# CH2-Isolation.net
KiCad netlist of a schematic drawn in Altium Designer
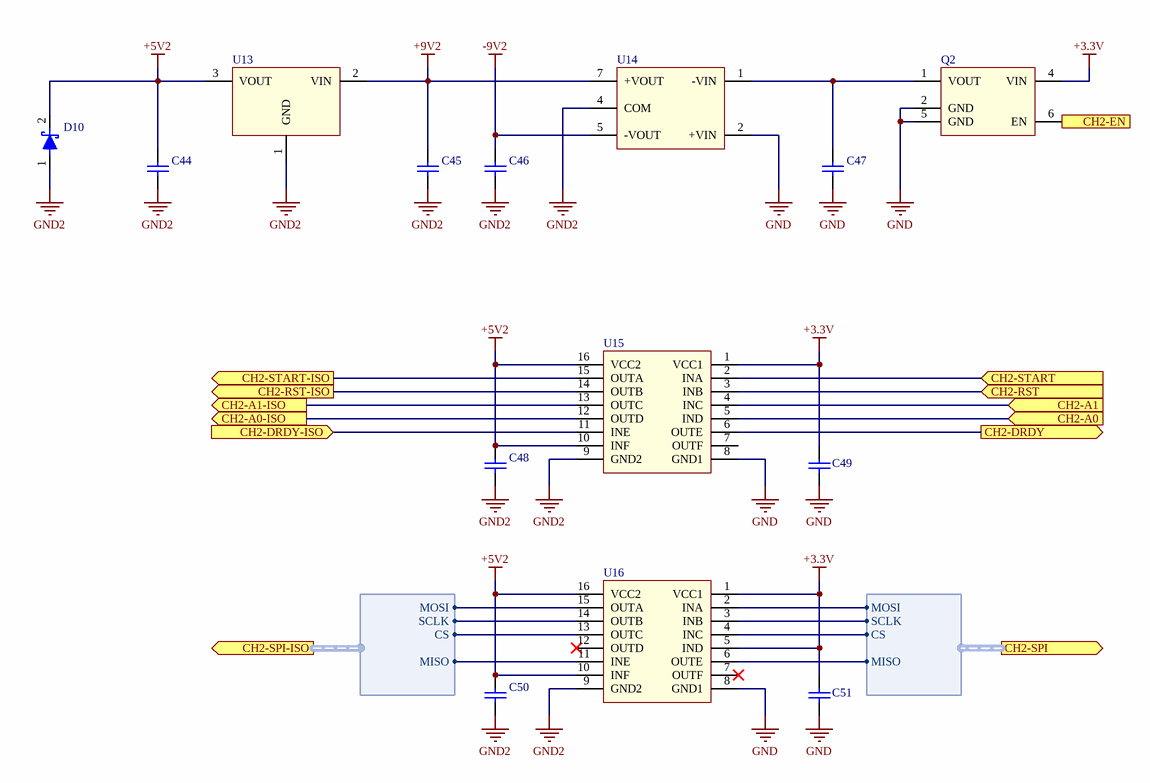
[diagram p0: CH2-Isolation.SchDoc]

(export (version "E")
  (design (tool "Eeschema 10.0.6"))
  (components
    (comp (ref "C44")
      (value "C0603C105M3RAC7867")
      (footprint "CAP-0603")
      (description "CAP CER 1uF 25V X7R 0603")
      (fields (field (name "MANUFACTURER") "Kemet") (field (name "TOLERANCE") "20%"))
      (libsource (lib "Kemet") (part "C0603C105M3RAC7867"))
    )
    (comp (ref "C45")
      (value "C0603C105M3RAC7867")
      (footprint "CAP-0603")
      (description "CAP CER 1uF 25V X7R 0603")
      (fields (field (name "MANUFACTURER") "Kemet") (field (name "TOLERANCE") "20%"))
      (libsource (lib "Kemet") (part "C0603C105M3RAC7867"))
    )
    (comp (ref "C46")
      (value "C0603C105M3RAC7867")
      (footprint "CAP-0603")
      (description "CAP CER 1uF 25V X7R 0603")
      (fields (field (name "MANUFACTURER") "Kemet") (field (name "TOLERANCE") "20%"))
      (libsource (lib "Kemet") (part "C0603C105M3RAC7867"))
    )
    (comp (ref "C47")
      (value "C0603C105M3RAC7867")
      (footprint "CAP-0603")
      (description "CAP CER 1uF 25V X7R 0603")
      (fields (field (name "MANUFACTURER") "Kemet") (field (name "TOLERANCE") "20%"))
      (libsource (lib "Kemet") (part "C0603C105M3RAC7867"))
    )
    (comp (ref "C48")
      (value "C0603C105M3RAC7867")
      (footprint "CAP-0603")
      (description "CAP CER 1uF 25V X7R 0603")
      (fields (field (name "MANUFACTURER") "Kemet") (field (name "TOLERANCE") "20%"))
      (libsource (lib "Kemet") (part "C0603C105M3RAC7867"))
    )
    (comp (ref "C49")
      (value "C0603C105M3RAC7867")
      (footprint "CAP-0603")
      (description "CAP CER 1uF 25V X7R 0603")
      (fields (field (name "MANUFACTURER") "Kemet") (field (name "TOLERANCE") "20%"))
      (libsource (lib "Kemet") (part "C0603C105M3RAC7867"))
    )
    (comp (ref "C50")
      (value "C0603C105M3RAC7867")
      (footprint "CAP-0603")
      (description "CAP CER 1uF 25V X7R 0603")
      (fields (field (name "MANUFACTURER") "Kemet") (field (name "TOLERANCE") "20%"))
      (libsource (lib "Kemet") (part "C0603C105M3RAC7867"))
    )
    (comp (ref "C51")
      (value "C0603C105M3RAC7867")
      (footprint "CAP-0603")
      (description "CAP CER 1uF 25V X7R 0603")
      (fields (field (name "MANUFACTURER") "Kemet") (field (name "TOLERANCE") "20%"))
      (libsource (lib "Kemet") (part "C0603C105M3RAC7867"))
    )
    (comp (ref "D10")
      (value "~")
      (footprint "SOD323 - DIODE UNIDIR")
      (description "Schottky Diode 30V 200mA SOT323")
      (fields (field (name "MANUFACTURER") "OnSemiconductor"))
      (libsource (lib "OnSemiconductors") (part "MM3Z5V6T1G"))
    )
    (comp (ref "Q2")
      (value "~")
      (footprint "TSSOP6")
      (fields (field (name "MANUFACTURER") "Microchip"))
      (libsource (lib "Microchip") (part "MIC94092YC6-TR"))
    )
    (comp (ref "U13")
      (value "~")
      (footprint "SOT23-5")
      (description "IC REG LDO 0.5V 0.15A TSOT23-5")
      (fields (field (name "MANUFACTURER") "ON Semiconductor"))
      (libsource (lib "OnSemiconductors") (part "NCP716BCSN500T1G"))
    )
    (comp (ref "U14")
      (value "R1D-3.309/P")
      (footprint "RECOM-R1D")
      (description "DC DC CONVERTER +/-9V 1W")
      (fields (field (name "MANUFACTURER") "Recom"))
      (libsource (lib "Recom") (part "R1D-3.309/P"))
    )
    (comp (ref "U15")
      (value "~")
      (footprint "SSOP16")
      (description "Digital Isolator, six-channel, 4/2, 16-SSOP")
      (fields (field (name "MANUFACTURER") "Texas Instruments"))
      (libsource (lib "TexasInstruments") (part "ISO7762FDBQ"))
    )
    (comp (ref "U16")
      (value "~")
      (footprint "SSOP16")
      (description "Digital Isolator, six-channel, 4/2, 16-SSOP")
      (fields (field (name "MANUFACTURER") "Texas Instruments"))
      (libsource (lib "TexasInstruments") (part "ISO7762FDBQ"))
    )
  )
  (nets
    (net (code "3") (name "+3.3V") (class "Default")
      (node (ref "C49") (pin "2") (pinfunction "2_2") (pintype "passive"))
      (node (ref "C51") (pin "2") (pinfunction "2_2") (pintype "passive"))
      (node (ref "Q2") (pin "4") (pinfunction "VIN_4") (pintype "passive"))
      (node (ref "U15") (pin "1") (pinfunction "VCC1_1") (pintype "passive"))
      (node (ref "U16") (pin "1") (pinfunction "VCC1_1") (pintype "passive"))
      (node (ref "U16") (pin "5") (pinfunction "IND_5") (pintype "passive"))
    )
    (net (code "4") (name "+5V2") (class "Default")
      (node (ref "C44") (pin "2") (pinfunction "2_2") (pintype "passive"))
      (node (ref "C48") (pin "2") (pinfunction "2_2") (pintype "passive"))
      (node (ref "C50") (pin "2") (pinfunction "2_2") (pintype "passive"))
      (node (ref "D10") (pin "2") (pinfunction "K_2") (pintype "passive"))
      (node (ref "U13") (pin "3") (pinfunction "VOUT_3") (pintype "passive"))
      (node (ref "U15") (pin "10") (pinfunction "INF_10") (pintype "passive"))
      (node (ref "U15") (pin "16") (pinfunction "VCC2_16") (pintype "passive"))
      (node (ref "U16") (pin "10") (pinfunction "INF_10") (pintype "passive"))
      (node (ref "U16") (pin "16") (pinfunction "VCC2_16") (pintype "passive"))
    )
    (net (code "5") (name "+9V2") (class "Default")
      (node (ref "C45") (pin "2") (pinfunction "2_2") (pintype "passive"))
      (node (ref "U13") (pin "2") (pinfunction "VIN_2") (pintype "passive"))
      (node (ref "U14") (pin "7") (pinfunction "+VOUT_7") (pintype "passive"))
    )
    (net (code "6") (name "-9V2") (class "Default")
      (node (ref "C46") (pin "2") (pinfunction "2_2") (pintype "passive"))
      (node (ref "U14") (pin "5") (pinfunction "-VOUT_5") (pintype "passive"))
    )
    (net (code "7") (name "/CH2-A0") (class "Default")
      (node (ref "U15") (pin "5") (pinfunction "IND_5") (pintype "passive"))
    )
    (net (code "8") (name "/CH2-A0-ISO") (class "Default")
      (node (ref "U15") (pin "12") (pinfunction "OUTD_12") (pintype "passive"))
    )
    (net (code "9") (name "/CH2-A1") (class "Default")
      (node (ref "U15") (pin "4") (pinfunction "INC_4") (pintype "passive"))
    )
    (net (code "10") (name "/CH2-A1-ISO") (class "Default")
      (node (ref "U15") (pin "13") (pinfunction "OUTC_13") (pintype "passive"))
    )
    (net (code "11") (name "/CH2-DRDY") (class "Default")
      (node (ref "U15") (pin "6") (pinfunction "OUTE_6") (pintype "passive"))
    )
    (net (code "12") (name "/CH2-DRDY-ISO") (class "Default")
      (node (ref "U15") (pin "11") (pinfunction "INE_11") (pintype "passive"))
    )
    (net (code "13") (name "/CH2-EN") (class "Default")
      (node (ref "Q2") (pin "6") (pinfunction "EN_6") (pintype "passive"))
    )
    (net (code "14") (name "/CH2-RST") (class "Default")
      (node (ref "U15") (pin "3") (pinfunction "INB_3") (pintype "passive"))
    )
    (net (code "15") (name "/CH2-RST-ISO") (class "Default")
      (node (ref "U15") (pin "14") (pinfunction "OUTB_14") (pintype "passive"))
    )
    (net (code "16") (name "/CH2-START") (class "Default")
      (node (ref "U15") (pin "2") (pinfunction "INA_2") (pintype "passive"))
    )
    (net (code "17") (name "/CH2-START-ISO") (class "Default")
      (node (ref "U15") (pin "15") (pinfunction "OUTA_15") (pintype "passive"))
    )
    (net (code "20") (name "GND") (class "Default")
      (node (ref "C47") (pin "1") (pinfunction "1_1") (pintype "passive"))
      (node (ref "C49") (pin "1") (pinfunction "1_1") (pintype "passive"))
      (node (ref "C51") (pin "1") (pinfunction "1_1") (pintype "passive"))
      (node (ref "Q2") (pin "2") (pinfunction "GND_2") (pintype "passive"))
      (node (ref "Q2") (pin "5") (pinfunction "GND_5") (pintype "passive"))
      (node (ref "U14") (pin "2") (pinfunction "+VIN_2") (pintype "passive"))
      (node (ref "U15") (pin "8") (pinfunction "GND1_8") (pintype "passive"))
      (node (ref "U16") (pin "8") (pinfunction "GND1_8") (pintype "passive"))
    )
    (net (code "21") (name "GND2") (class "Default")
      (node (ref "C44") (pin "1") (pinfunction "1_1") (pintype "passive"))
      (node (ref "C45") (pin "1") (pinfunction "1_1") (pintype "passive"))
      (node (ref "C46") (pin "1") (pinfunction "1_1") (pintype "passive"))
      (node (ref "C48") (pin "1") (pinfunction "1_1") (pintype "passive"))
      (node (ref "C50") (pin "1") (pinfunction "1_1") (pintype "passive"))
      (node (ref "D10") (pin "1") (pinfunction "A_1") (pintype "passive"))
      (node (ref "U13") (pin "1") (pinfunction "GND_1") (pintype "passive"))
      (node (ref "U14") (pin "4") (pinfunction "COM_4") (pintype "passive"))
      (node (ref "U15") (pin "9") (pinfunction "GND2_9") (pintype "passive"))
      (node (ref "U16") (pin "9") (pinfunction "GND2_9") (pintype "passive"))
    )
    (net (code "22") (name "Net-(Q2-VOUT)") (class "Default")
      (node (ref "C47") (pin "2") (pinfunction "2_2") (pintype "passive"))
      (node (ref "Q2") (pin "1") (pinfunction "VOUT_1") (pintype "passive"))
      (node (ref "U14") (pin "1") (pinfunction "-VIN_1") (pintype "passive"))
    )
    (net (code "23") (name "unconnected-(U15-OUTF-Pad7)") (class "Default")
      (node (ref "U15") (pin "7") (pinfunction "OUTF_7") (pintype "passive"))
    )
    (net (code "24") (name "unconnected-(U16-INA-Pad2)") (class "Default")
      (node (ref "U16") (pin "2") (pinfunction "INA_2") (pintype "passive"))
    )
    (net (code "25") (name "unconnected-(U16-INB-Pad3)") (class "Default")
      (node (ref "U16") (pin "3") (pinfunction "INB_3") (pintype "passive"))
    )
    (net (code "26") (name "unconnected-(U16-INC-Pad4)") (class "Default")
      (node (ref "U16") (pin "4") (pinfunction "INC_4") (pintype "passive"))
    )
    (net (code "27") (name "unconnected-(U16-INE-Pad11)") (class "Default")
      (node (ref "U16") (pin "11") (pinfunction "INE_11") (pintype "passive"))
    )
    (net (code "28") (name "unconnected-(U16-OUTA-Pad15)") (class "Default")
      (node (ref "U16") (pin "15") (pinfunction "OUTA_15") (pintype "passive"))
    )
    (net (code "29") (name "unconnected-(U16-OUTB-Pad14)") (class "Default")
      (node (ref "U16") (pin "14") (pinfunction "OUTB_14") (pintype "passive"))
    )
    (net (code "30") (name "unconnected-(U16-OUTC-Pad13)") (class "Default")
      (node (ref "U16") (pin "13") (pinfunction "OUTC_13") (pintype "passive"))
    )
    (net (code "31") (name "unconnected-(U16-OUTD-Pad12)") (class "Default")
      (node (ref "U16") (pin "12") (pinfunction "OUTD_12") (pintype "passive+no_connect"))
    )
    (net (code "32") (name "unconnected-(U16-OUTE-Pad6)") (class "Default")
      (node (ref "U16") (pin "6") (pinfunction "OUTE_6") (pintype "passive"))
    )
    (net (code "33") (name "unconnected-(U16-OUTF-Pad7)") (class "Default")
      (node (ref "U16") (pin "7") (pinfunction "OUTF_7") (pintype "passive+no_connect"))
    )
  )
)
